# 24_064.net
KiCad netlist of a schematic drawn in Altium Designer
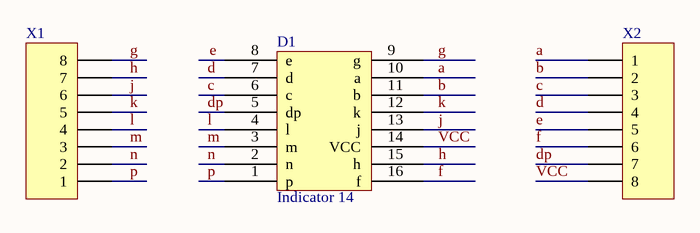
[diagram p0: 24.064.SchDoc]

(export (version "E")
  (design (tool "Eeschema 10.0.6"))
  (components
    (comp (ref "D1")
      (value "Indicator 14")
      (footprint "INDICATIR 14")
      (libsource (lib "msp_SchLib") (part "Indicator 14"))
    )
    (comp (ref "X1")
      (value "Header 8")
      (footprint "HDR1X8")
      (description "Header, 8-Pin")
      (fields (field (name "PUBLISHER") "Altium Limited"))
      (libsource (lib "") (part "Header 8_1"))
    )
    (comp (ref "X2")
      (value "Header 8")
      (footprint "HDR1X8")
      (description "Header, 8-Pin")
      (fields (field (name "PUBLISHER") "Altium Limited"))
      (libsource (lib "Miscellaneous Connectors") (part "Header 8"))
    )
  )
  (nets
    (net (code "1") (name "/VCC") (class "Default")
      (node (ref "D1") (pin "14") (pinfunction "VCC_14") (pintype "passive"))
      (node (ref "X2") (pin "8") (pinfunction "8_8") (pintype "passive"))
    )
    (net (code "2") (name "/a") (class "Default")
      (node (ref "D1") (pin "10") (pinfunction "a_10") (pintype "passive"))
      (node (ref "X2") (pin "1") (pinfunction "1_1") (pintype "passive"))
    )
    (net (code "3") (name "/b") (class "Default")
      (node (ref "D1") (pin "11") (pinfunction "b_11") (pintype "passive"))
      (node (ref "X2") (pin "2") (pinfunction "2_2") (pintype "passive"))
    )
    (net (code "4") (name "/c") (class "Default")
      (node (ref "D1") (pin "6") (pinfunction "c_6") (pintype "passive"))
      (node (ref "X2") (pin "3") (pinfunction "3_3") (pintype "passive"))
    )
    (net (code "5") (name "/d") (class "Default")
      (node (ref "D1") (pin "7") (pinfunction "d_7") (pintype "passive"))
      (node (ref "X2") (pin "4") (pinfunction "4_4") (pintype "passive"))
    )
    (net (code "6") (name "/dp") (class "Default")
      (node (ref "D1") (pin "5") (pinfunction "dp_5") (pintype "passive"))
      (node (ref "X2") (pin "7") (pinfunction "7_7") (pintype "passive"))
    )
    (net (code "7") (name "/e") (class "Default")
      (node (ref "D1") (pin "8") (pinfunction "e_8") (pintype "passive"))
      (node (ref "X2") (pin "5") (pinfunction "5_5") (pintype "passive"))
    )
    (net (code "8") (name "/f") (class "Default")
      (node (ref "D1") (pin "16") (pinfunction "f_16") (pintype "passive"))
      (node (ref "X2") (pin "6") (pinfunction "6_6") (pintype "passive"))
    )
    (net (code "9") (name "/g") (class "Default")
      (node (ref "D1") (pin "9") (pinfunction "g_9") (pintype "passive"))
      (node (ref "X1") (pin "8") (pinfunction "8_8") (pintype "passive"))
    )
    (net (code "10") (name "/h") (class "Default")
      (node (ref "D1") (pin "15") (pinfunction "h_15") (pintype "passive"))
      (node (ref "X1") (pin "7") (pinfunction "7_7") (pintype "passive"))
    )
    (net (code "11") (name "/j") (class "Default")
      (node (ref "D1") (pin "13") (pinfunction "j_13") (pintype "passive"))
      (node (ref "X1") (pin "6") (pinfunction "6_6") (pintype "passive"))
    )
    (net (code "12") (name "/k") (class "Default")
      (node (ref "D1") (pin "12") (pinfunction "k_12") (pintype "passive"))
      (node (ref "X1") (pin "5") (pinfunction "5_5") (pintype "passive"))
    )
    (net (code "13") (name "/l") (class "Default")
      (node (ref "D1") (pin "4") (pinfunction "l_4") (pintype "passive"))
      (node (ref "X1") (pin "4") (pinfunction "4_4") (pintype "passive"))
    )
    (net (code "14") (name "/m") (class "Default")
      (node (ref "D1") (pin "3") (pinfunction "m_3") (pintype "passive"))
      (node (ref "X1") (pin "3") (pinfunction "3_3") (pintype "passive"))
    )
    (net (code "15") (name "/n") (class "Default")
      (node (ref "D1") (pin "2") (pinfunction "n_2") (pintype "passive"))
      (node (ref "X1") (pin "2") (pinfunction "2_2") (pintype "passive"))
    )
    (net (code "16") (name "/p") (class "Default")
      (node (ref "D1") (pin "1") (pinfunction "p_1") (pintype "passive"))
      (node (ref "X1") (pin "1") (pinfunction "1_1") (pintype "passive"))
    )
  )
)
